# PulseGenerator.net
KiCad netlist of a schematic drawn in Altium Designer
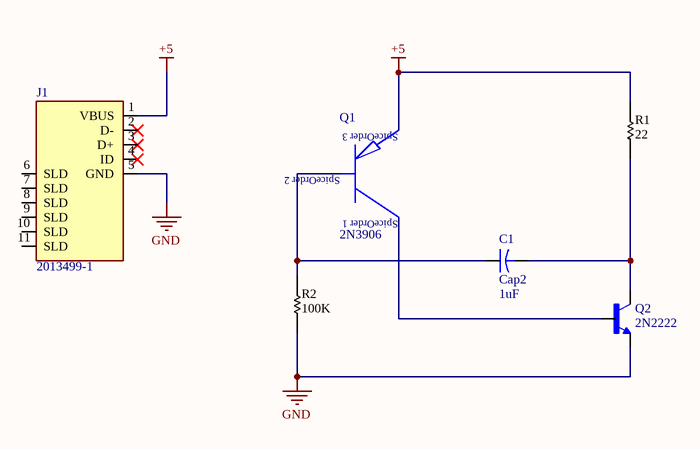
[diagram p0: PulseGenerator.SchDoc]

(export (version "E")
  (design (tool "Eeschema 10.0.6"))
  (components
    (comp (ref "C1")
      (value "Cap2")
      (footprint "CAPR5-4X5")
      (description "Capacitor")
      (fields (field (name "ALTIUM_VALUE") "1uF") (field (name "PUBLISHER") "Altium Limited"))
      (libsource (lib "Miscellaneous Devices") (part "Cap2"))
    )
    (comp (ref "J1")
      (value "2013499-1")
      (footprint "TE_2013499-1")
      (description "Conn Micro USB 2.0 Type B RCP 5 POS 0.65mm Solder RA SMD 5 Terminal 1 Port T/R")
      (fields (field (name "MF") "TE Connectivity"))
      (libsource (lib "2013499-1") (part "2013499-1"))
    )
    (comp (ref "Q1")
      (value "2N3906")
      (footprint "TO92")
      (description "Bipolar _BJT_ Transistor PNP 40V 200mA 250MHz 625mW Through Hole TO-92")
      (fields (field (name "MF") "Diotec Semiconductor"))
      (libsource (lib "2N3906") (part "2N3906"))
    )
    (comp (ref "Q2")
      (value "2N2222")
      (footprint "TO127P580H530-3")
      (description "Bipolar _BJT_ Transistor NPN 50V 800mA 500mW Through Hole TO-18 _TO-206AA_")
      (fields
        (field (name "MF") "MICROSS/On Semiconductor")
        (field (name "DIGI-KEY_PART_NUMBER") "1086-15156-ND")
      )
      (libsource (lib "2N2222") (part "2N2222"))
    )
    (comp (ref "R1")
      (value "22")
      (footprint "RES1016-6800X250_PHO")
      (libsource (lib "RES_CF_MCF_5%_0.25W_250V_500VMAX_MUL") (part "0ohm_MCF0.25W0R_MUL"))
    )
    (comp (ref "R2")
      (value "100K")
      (footprint "RES1016-6800X250_PHO")
      (libsource (lib "RES_CF_MCF_5%_0.25W_250V_500VMAX_MUL") (part "0ohm_MCF0.25W0R_MUL"))
    )
  )
  (nets
    (net (code "1") (name "+5") (class "Default")
      (node (ref "J1") (pin "1") (pinfunction "VBUS_1") (pintype "power_in"))
      (node (ref "Q1") (pin "3") (pinfunction "E_3") (pintype "passive"))
      (node (ref "R1") (pin "2") (pinfunction "2_2") (pintype "passive"))
    )
    (net (code "2") (name "GND") (class "Default")
      (node (ref "J1") (pin "5") (pinfunction "GND_5") (pintype "power_in"))
      (node (ref "Q2") (pin "1") (pinfunction "E_1") (pintype "passive"))
      (node (ref "R2") (pin "1") (pinfunction "1_1") (pintype "passive"))
    )
    (net (code "3") (name "Net-(Q1-B)") (class "Default")
      (node (ref "C1") (pin "1") (pinfunction "1_1") (pintype "passive"))
      (node (ref "Q1") (pin "2") (pinfunction "B_2") (pintype "passive"))
      (node (ref "R2") (pin "2") (pinfunction "2_2") (pintype "passive"))
    )
    (net (code "4") (name "Net-(Q1-C)") (class "Default")
      (node (ref "Q1") (pin "1") (pinfunction "C_1") (pintype "passive"))
      (node (ref "Q2") (pin "2") (pinfunction "B_2") (pintype "passive"))
    )
    (net (code "5") (name "Net-(Q2-C)") (class "Default")
      (node (ref "C1") (pin "2") (pinfunction "2_2") (pintype "passive"))
      (node (ref "Q2") (pin "3") (pinfunction "C_3") (pintype "passive"))
      (node (ref "R1") (pin "1") (pinfunction "1_1") (pintype "passive"))
    )
    (net (code "6") (name "unconnected-(J1-D+-Pad3)") (class "Default")
      (node (ref "J1") (pin "3") (pinfunction "D+_3") (pintype "passive+no_connect"))
    )
    (net (code "7") (name "unconnected-(J1-D--Pad2)") (class "Default")
      (node (ref "J1") (pin "2") (pinfunction "D-_2") (pintype "passive+no_connect"))
    )
    (net (code "8") (name "unconnected-(J1-ID-Pad4)") (class "Default")
      (node (ref "J1") (pin "4") (pinfunction "ID_4") (pintype "passive+no_connect"))
    )
    (net (code "9") (name "unconnected-(J1-SLD-Pad6)") (class "Default")
      (node (ref "J1") (pin "6") (pinfunction "SLD_6") (pintype "passive"))
    )
    (net (code "10") (name "unconnected-(J1-SLD-Pad7)") (class "Default")
      (node (ref "J1") (pin "7") (pinfunction "SLD_7") (pintype "passive"))
    )
    (net (code "11") (name "unconnected-(J1-SLD-Pad8)") (class "Default")
      (node (ref "J1") (pin "8") (pinfunction "SLD_8") (pintype "passive"))
    )
    (net (code "12") (name "unconnected-(J1-SLD-Pad9)") (class "Default")
      (node (ref "J1") (pin "9") (pinfunction "SLD_9") (pintype "passive"))
    )
    (net (code "13") (name "unconnected-(J1-SLD-Pad10)") (class "Default")
      (node (ref "J1") (pin "10") (pinfunction "SLD_10") (pintype "passive"))
    )
    (net (code "14") (name "unconnected-(J1-SLD-Pad11)") (class "Default")
      (node (ref "J1") (pin "11") (pinfunction "SLD_11") (pintype "passive"))
    )
  )
)
